# ProPrj_Backlight_esp32_dm135_2026-01-07.net
KiCad netlist of a schematic drawn in EasyEDA Pro
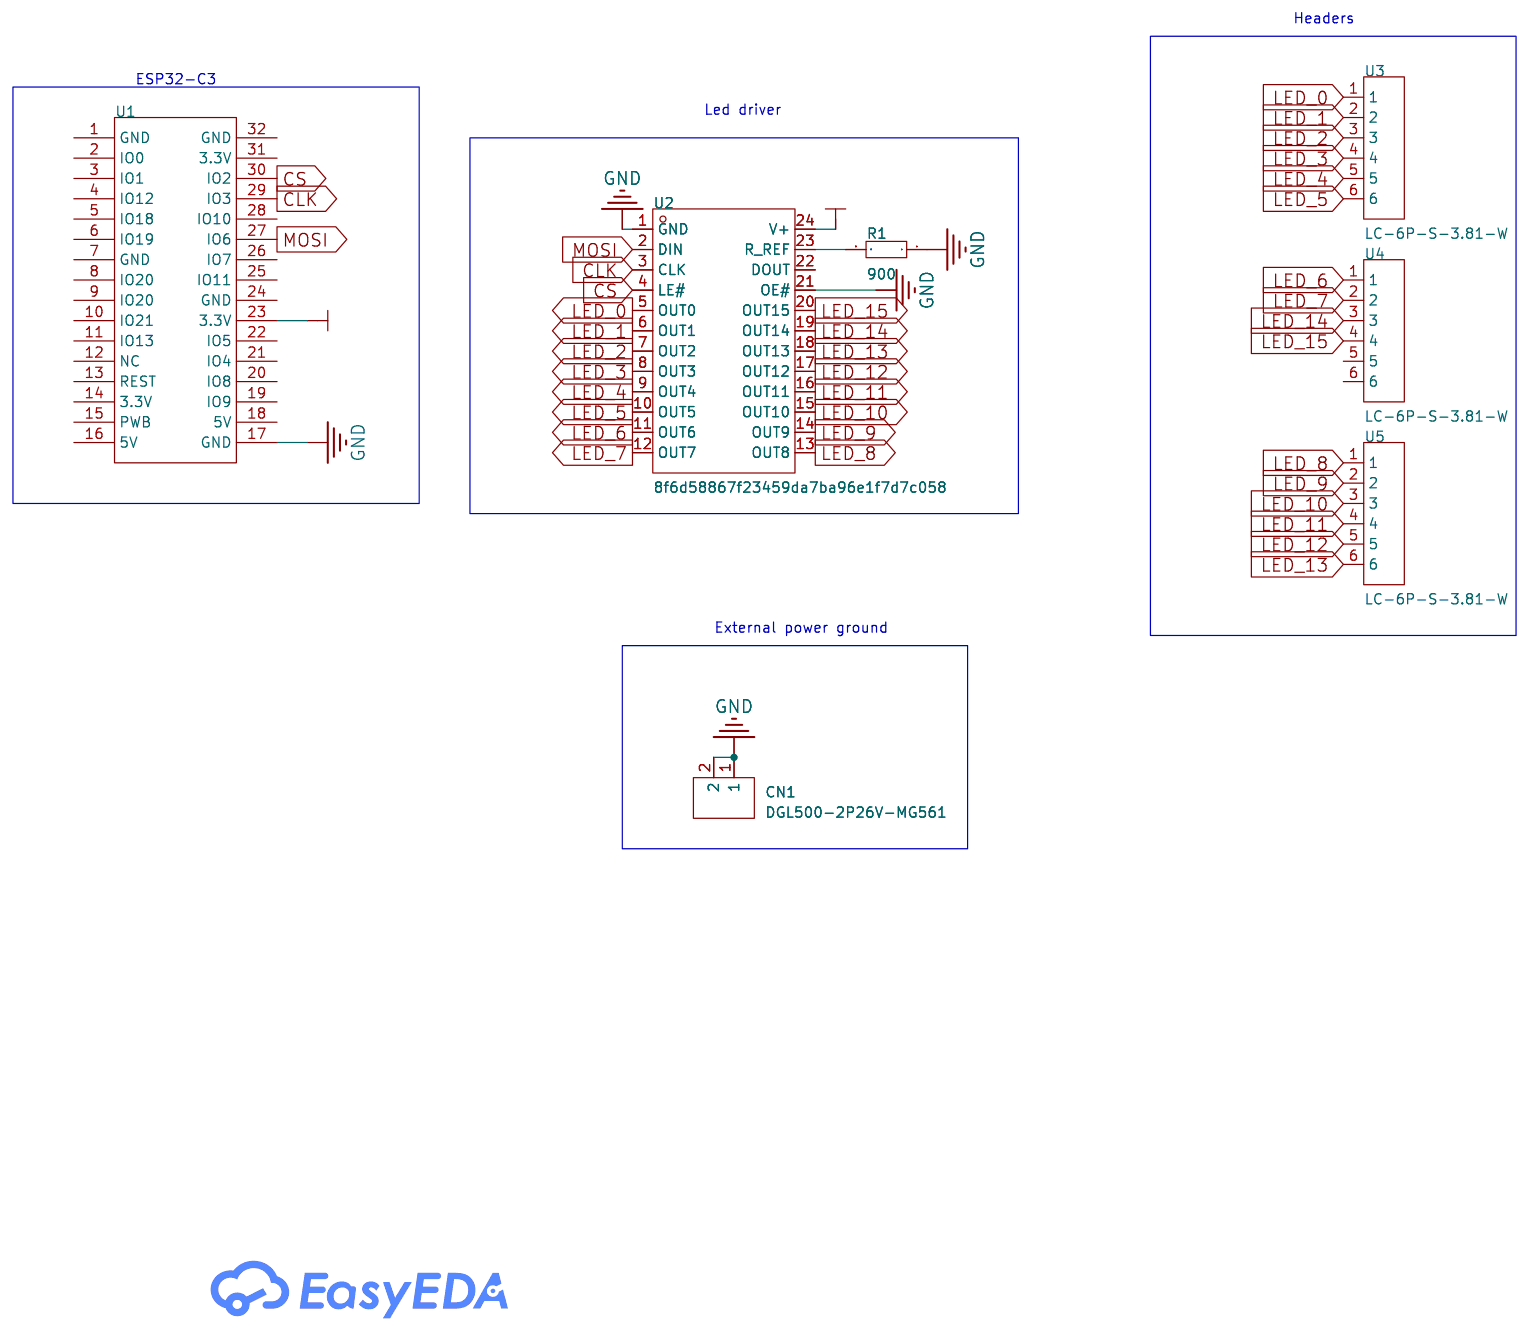
[diagram p0: schematic sheet]

(export (version "E")
  (design (tool "Eeschema 10.0.6"))
  (components
    (comp (ref "CN1")
      (value "DGL500-2P26V-MG561")
      (footprint "easyedapro:CONN-TH_2P-P5.00_DGL500-2P26V-MG561")
      (fields (field (name "Manufacturer") "XUNPU(讯普)"))
      (libsource (lib "easyedapro") (part "DGL500-2P26V-MG561"))
    )
    (comp (ref "R1") (value "900") (footprint "easyedapro:R0603") (libsource (lib "easyedapro") (part "Res")))
    (comp (ref "U1") (value "~") (libsource (lib "easyedapro") (part "ESP32-C3-LUATOS")))
    (comp (ref "U2")
      (value "8f6d58867f23459da7ba96e1f7d7c058")
      (footprint "easyedapro:SOIC-24_L15.4-W7.5-P1.27-LS10.3-BL")
      (libsource (lib "easyedapro") (part "DM135B"))
    )
    (comp (ref "U3")
      (value "LC-6P-S-3.81-W")
      (footprint "easyedapro:CONN-TH_6P-P3.81_KF2EDGR-3.81-6P")
      (libsource (lib "easyedapro") (part "LC-6P-S-3.81-W"))
    )
    (comp (ref "U4")
      (value "LC-6P-S-3.81-W")
      (footprint "easyedapro:CONN-TH_6P-P3.81_KF2EDGR-3.81-6P")
      (libsource (lib "easyedapro") (part "LC-6P-S-3.81-W"))
    )
    (comp (ref "U5")
      (value "LC-6P-S-3.81-W")
      (footprint "easyedapro:CONN-TH_6P-P3.81_KF2EDGR-3.81-6P")
      (libsource (lib "easyedapro") (part "LC-6P-S-3.81-W"))
    )
  )
  (nets
    (net (code "1") (name "+3.3V") (class "Default")
      (node (ref "U1") (pin "23") (pinfunction "3.3V_23") (pintype "input"))
      (node (ref "U2") (pin "24") (pinfunction "V+_24") (pintype "unspecified"))
    )
    (net (code "2") (name "CLK") (class "Default")
      (node (ref "U1") (pin "29") (pinfunction "IO3_29") (pintype "input"))
      (node (ref "U2") (pin "3") (pinfunction "CLK_3") (pintype "unspecified"))
    )
    (net (code "3") (name "CS") (class "Default")
      (node (ref "U1") (pin "30") (pinfunction "IO2_30") (pintype "input"))
      (node (ref "U2") (pin "4") (pinfunction "LE#_4") (pintype "unspecified"))
    )
    (net (code "4") (name "GND") (class "Default")
      (node (ref "CN1") (pin "1") (pinfunction "1_1") (pintype "unspecified"))
      (node (ref "CN1") (pin "2") (pinfunction "2_2") (pintype "unspecified"))
      (node (ref "R1") (pin "1") (pinfunction "1_1") (pintype "input"))
      (node (ref "U1") (pin "17") (pinfunction "GND_17") (pintype "input"))
      (node (ref "U2") (pin "1") (pinfunction "GND_1") (pintype "unspecified"))
      (node (ref "U2") (pin "21") (pinfunction "OE#_21") (pintype "unspecified"))
    )
    (net (code "5") (name "LED_0") (class "Default")
      (node (ref "U2") (pin "5") (pinfunction "OUT0_5") (pintype "unspecified"))
      (node (ref "U3") (pin "1") (pinfunction "1_1") (pintype "unspecified"))
    )
    (net (code "6") (name "LED_1") (class "Default")
      (node (ref "U2") (pin "6") (pinfunction "OUT1_6") (pintype "unspecified"))
      (node (ref "U3") (pin "2") (pinfunction "2_2") (pintype "unspecified"))
    )
    (net (code "7") (name "LED_2") (class "Default")
      (node (ref "U2") (pin "7") (pinfunction "OUT2_7") (pintype "unspecified"))
      (node (ref "U3") (pin "3") (pinfunction "3_3") (pintype "unspecified"))
    )
    (net (code "8") (name "LED_3") (class "Default")
      (node (ref "U2") (pin "8") (pinfunction "OUT3_8") (pintype "unspecified"))
      (node (ref "U3") (pin "4") (pinfunction "4_4") (pintype "unspecified"))
    )
    (net (code "9") (name "LED_4") (class "Default")
      (node (ref "U2") (pin "9") (pinfunction "OUT4_9") (pintype "unspecified"))
      (node (ref "U3") (pin "5") (pinfunction "5_5") (pintype "unspecified"))
    )
    (net (code "10") (name "LED_5") (class "Default")
      (node (ref "U2") (pin "10") (pinfunction "OUT5_10") (pintype "unspecified"))
      (node (ref "U3") (pin "6") (pinfunction "6_6") (pintype "unspecified"))
    )
    (net (code "11") (name "LED_6") (class "Default")
      (node (ref "U2") (pin "11") (pinfunction "OUT6_11") (pintype "unspecified"))
      (node (ref "U4") (pin "1") (pinfunction "1_1") (pintype "unspecified"))
    )
    (net (code "12") (name "LED_7") (class "Default")
      (node (ref "U2") (pin "12") (pinfunction "OUT7_12") (pintype "unspecified"))
      (node (ref "U4") (pin "2") (pinfunction "2_2") (pintype "unspecified"))
    )
    (net (code "13") (name "LED_8") (class "Default")
      (node (ref "U2") (pin "13") (pinfunction "OUT8_13") (pintype "unspecified"))
      (node (ref "U5") (pin "1") (pinfunction "1_1") (pintype "unspecified"))
    )
    (net (code "14") (name "LED_9") (class "Default")
      (node (ref "U2") (pin "14") (pinfunction "OUT9_14") (pintype "unspecified"))
      (node (ref "U5") (pin "2") (pinfunction "2_2") (pintype "unspecified"))
    )
    (net (code "15") (name "LED_10") (class "Default")
      (node (ref "U2") (pin "15") (pinfunction "OUT10_15") (pintype "unspecified"))
      (node (ref "U5") (pin "3") (pinfunction "3_3") (pintype "unspecified"))
    )
    (net (code "16") (name "LED_11") (class "Default")
      (node (ref "U2") (pin "16") (pinfunction "OUT11_16") (pintype "unspecified"))
      (node (ref "U5") (pin "4") (pinfunction "4_4") (pintype "unspecified"))
    )
    (net (code "17") (name "LED_12") (class "Default")
      (node (ref "U2") (pin "17") (pinfunction "OUT12_17") (pintype "unspecified"))
      (node (ref "U5") (pin "5") (pinfunction "5_5") (pintype "unspecified"))
    )
    (net (code "18") (name "LED_13") (class "Default")
      (node (ref "U2") (pin "18") (pinfunction "OUT13_18") (pintype "unspecified"))
      (node (ref "U5") (pin "6") (pinfunction "6_6") (pintype "unspecified"))
    )
    (net (code "19") (name "LED_14") (class "Default")
      (node (ref "U2") (pin "19") (pinfunction "OUT14_19") (pintype "unspecified"))
      (node (ref "U4") (pin "3") (pinfunction "3_3") (pintype "unspecified"))
    )
    (net (code "20") (name "LED_15") (class "Default")
      (node (ref "U2") (pin "20") (pinfunction "OUT15_20") (pintype "unspecified"))
      (node (ref "U4") (pin "4") (pinfunction "4_4") (pintype "unspecified"))
    )
    (net (code "21") (name "MOSI") (class "Default")
      (node (ref "U1") (pin "27") (pinfunction "IO6_27") (pintype "input"))
      (node (ref "U2") (pin "2") (pinfunction "DIN_2") (pintype "unspecified"))
    )
    (net (code "22") (name "Net-(U2-R_REF)") (class "Default")
      (node (ref "R1") (pin "2") (pinfunction "2_2") (pintype "input"))
      (node (ref "U2") (pin "23") (pinfunction "R_REF_23") (pintype "unspecified"))
    )
    (net (code "23") (name "unconnected-(U1-3.3V-Pad14)") (class "Default")
      (node (ref "U1") (pin "14") (pinfunction "3.3V_14") (pintype "input"))
    )
    (net (code "24") (name "unconnected-(U1-3.3V-Pad31)") (class "Default")
      (node (ref "U1") (pin "31") (pinfunction "3.3V_31") (pintype "input"))
    )
    (net (code "25") (name "unconnected-(U1-5V-Pad16)") (class "Default")
      (node (ref "U1") (pin "16") (pinfunction "5V_16") (pintype "input"))
    )
    (net (code "26") (name "unconnected-(U1-5V-Pad18)") (class "Default")
      (node (ref "U1") (pin "18") (pinfunction "5V_18") (pintype "input"))
    )
    (net (code "27") (name "unconnected-(U1-GND-Pad1)") (class "Default")
      (node (ref "U1") (pin "1") (pinfunction "GND_1") (pintype "input"))
    )
    (net (code "28") (name "unconnected-(U1-GND-Pad7)") (class "Default")
      (node (ref "U1") (pin "7") (pinfunction "GND_7") (pintype "input"))
    )
    (net (code "29") (name "unconnected-(U1-GND-Pad24)") (class "Default")
      (node (ref "U1") (pin "24") (pinfunction "GND_24") (pintype "input"))
    )
    (net (code "30") (name "unconnected-(U1-GND-Pad32)") (class "Default")
      (node (ref "U1") (pin "32") (pinfunction "GND_32") (pintype "input"))
    )
    (net (code "31") (name "unconnected-(U1-IO0-Pad2)") (class "Default")
      (node (ref "U1") (pin "2") (pinfunction "IO0_2") (pintype "input"))
    )
    (net (code "32") (name "unconnected-(U1-IO1-Pad3)") (class "Default")
      (node (ref "U1") (pin "3") (pinfunction "IO1_3") (pintype "input"))
    )
    (net (code "33") (name "unconnected-(U1-IO4-Pad21)") (class "Default")
      (node (ref "U1") (pin "21") (pinfunction "IO4_21") (pintype "input"))
    )
    (net (code "34") (name "unconnected-(U1-IO5-Pad22)") (class "Default")
      (node (ref "U1") (pin "22") (pinfunction "IO5_22") (pintype "input"))
    )
    (net (code "35") (name "unconnected-(U1-IO7-Pad26)") (class "Default")
      (node (ref "U1") (pin "26") (pinfunction "IO7_26") (pintype "input"))
    )
    (net (code "36") (name "unconnected-(U1-IO8-Pad20)") (class "Default")
      (node (ref "U1") (pin "20") (pinfunction "IO8_20") (pintype "input"))
    )
    (net (code "37") (name "unconnected-(U1-IO9-Pad19)") (class "Default")
      (node (ref "U1") (pin "19") (pinfunction "IO9_19") (pintype "input"))
    )
    (net (code "38") (name "unconnected-(U1-IO10-Pad28)") (class "Default")
      (node (ref "U1") (pin "28") (pinfunction "IO10_28") (pintype "input"))
    )
    (net (code "39") (name "unconnected-(U1-IO11-Pad25)") (class "Default")
      (node (ref "U1") (pin "25") (pinfunction "IO11_25") (pintype "input"))
    )
    (net (code "40") (name "unconnected-(U1-IO12-Pad4)") (class "Default")
      (node (ref "U1") (pin "4") (pinfunction "IO12_4") (pintype "input"))
    )
    (net (code "41") (name "unconnected-(U1-IO13-Pad11)") (class "Default")
      (node (ref "U1") (pin "11") (pinfunction "IO13_11") (pintype "input"))
    )
    (net (code "42") (name "unconnected-(U1-IO18-Pad5)") (class "Default")
      (node (ref "U1") (pin "5") (pinfunction "IO18_5") (pintype "input"))
    )
    (net (code "43") (name "unconnected-(U1-IO19-Pad6)") (class "Default")
      (node (ref "U1") (pin "6") (pinfunction "IO19_6") (pintype "input"))
    )
    (net (code "44") (name "unconnected-(U1-IO20-Pad8)") (class "Default")
      (node (ref "U1") (pin "8") (pinfunction "IO20_8") (pintype "input"))
    )
    (net (code "45") (name "unconnected-(U1-IO20-Pad9)") (class "Default")
      (node (ref "U1") (pin "9") (pinfunction "IO20_9") (pintype "input"))
    )
    (net (code "46") (name "unconnected-(U1-IO21-Pad10)") (class "Default")
      (node (ref "U1") (pin "10") (pinfunction "IO21_10") (pintype "input"))
    )
    (net (code "47") (name "unconnected-(U1-NC-Pad12)") (class "Default")
      (node (ref "U1") (pin "12") (pinfunction "NC_12") (pintype "input"))
    )
    (net (code "48") (name "unconnected-(U1-PWB-Pad15)") (class "Default")
      (node (ref "U1") (pin "15") (pinfunction "PWB_15") (pintype "input"))
    )
    (net (code "49") (name "unconnected-(U1-REST-Pad13)") (class "Default")
      (node (ref "U1") (pin "13") (pinfunction "REST_13") (pintype "input"))
    )
    (net (code "50") (name "unconnected-(U2-DOUT-Pad22)") (class "Default")
      (node (ref "U2") (pin "22") (pinfunction "DOUT_22") (pintype "unspecified"))
    )
    (net (code "51") (name "unconnected-(U4-Pad5)") (class "Default")
      (node (ref "U4") (pin "5") (pinfunction "5_5") (pintype "unspecified"))
    )
    (net (code "52") (name "unconnected-(U4-Pad6)") (class "Default")
      (node (ref "U4") (pin "6") (pinfunction "6_6") (pintype "unspecified"))
    )
  )
)
